# lcd-i2c.net
KiCad netlist of a schematic drawn in EAGLE
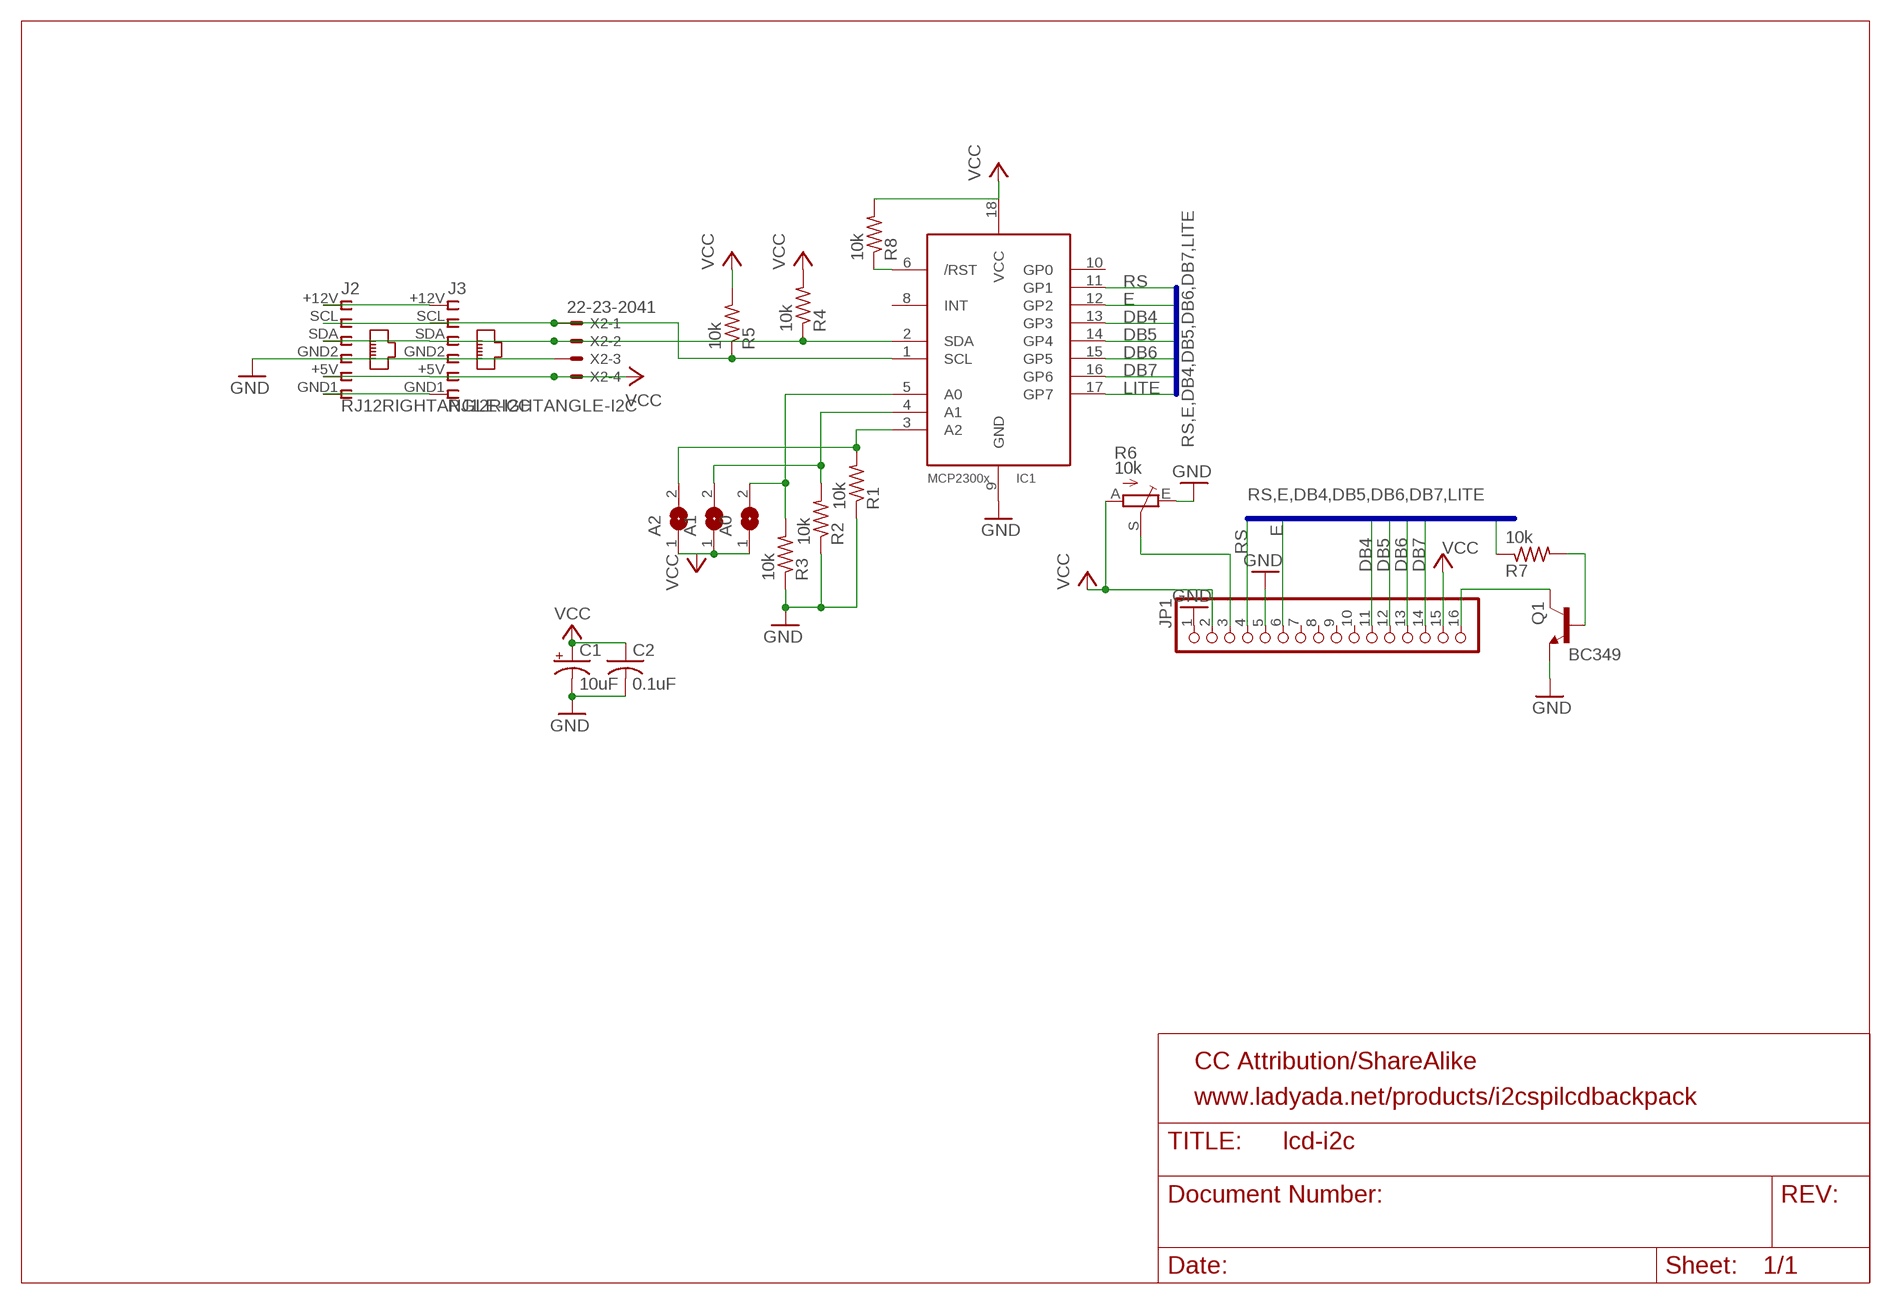
[diagram p0: schematic, sheet 1]

(export (version "E")
  (design (tool "Eeschema 10.0.6"))
  (components
    (comp (ref "A0") (value "SJ") (footprint "eagle-import:SJ") (libsource (lib "eagle-import") (part "SJ")))
    (comp (ref "A1") (value "SJ") (footprint "eagle-import:SJ") (libsource (lib "eagle-import") (part "SJ")))
    (comp (ref "A2") (value "SJ") (footprint "eagle-import:SJ") (libsource (lib "eagle-import") (part "SJ")))
    (comp (ref "C1")
      (value "10uF")
      (footprint "eagle-import:A_3216-18R")
      (libsource (lib "eagle-import") (part "CPOL-USA/3216-18R"))
    )
    (comp (ref "C2")
      (value "0.1uF")
      (footprint "eagle-import:C1206")
      (libsource (lib "eagle-import") (part "C-USC1206"))
    )
    (comp (ref "IC1")
      (value "MCP2300X/P")
      (footprint "eagle-import:DIL18")
      (libsource (lib "eagle-import") (part "MCP2300X/P"))
    )
    (comp (ref "J2")
      (value "RJ12RIGHTANGLE-I2C")
      (footprint "eagle-import:RJ12-RIGHTANGLE-I2C")
      (libsource (lib "eagle-import") (part "RJ12RIGHTANGLE-I2C"))
    )
    (comp (ref "J3")
      (value "RJ12RIGHTANGLE-I2C")
      (footprint "eagle-import:RJ12-RIGHTANGLE-I2C")
      (libsource (lib "eagle-import") (part "RJ12RIGHTANGLE-I2C"))
    )
    (comp (ref "JP1")
      (value "PINHD-1X16")
      (footprint "eagle-import:1X16")
      (libsource (lib "eagle-import") (part "PINHD-1X16"))
    )
    (comp (ref "Q1")
      (value "BC349")
      (footprint "eagle-import:TO92-EBC")
      (libsource (lib "eagle-import") (part "-NPN-TO92-EBCBC317"))
    )
    (comp (ref "R1")
      (value "10k")
      (footprint "eagle-import:M1206")
      (libsource (lib "eagle-import") (part "R-US_M1206"))
    )
    (comp (ref "R2")
      (value "10k")
      (footprint "eagle-import:M1206")
      (libsource (lib "eagle-import") (part "R-US_M1206"))
    )
    (comp (ref "R3")
      (value "10k")
      (footprint "eagle-import:M1206")
      (libsource (lib "eagle-import") (part "R-US_M1206"))
    )
    (comp (ref "R4")
      (value "10k")
      (footprint "eagle-import:M1206")
      (libsource (lib "eagle-import") (part "R-US_M1206"))
    )
    (comp (ref "R5")
      (value "10k")
      (footprint "eagle-import:M1206")
      (libsource (lib "eagle-import") (part "R-US_M1206"))
    )
    (comp (ref "R6")
      (value "10k")
      (footprint "eagle-import:CA6V")
      (libsource (lib "eagle-import") (part "TRIM_EU-CA6V"))
    )
    (comp (ref "R7")
      (value "10k")
      (footprint "eagle-import:M1206")
      (libsource (lib "eagle-import") (part "R-US_M1206"))
    )
    (comp (ref "R8")
      (value "10k")
      (footprint "eagle-import:M1206")
      (libsource (lib "eagle-import") (part "R-US_M1206"))
    )
    (comp (ref "X2")
      (value "22-23-2041")
      (footprint "eagle-import:22-23-2041")
      (fields (field (name "MF") "MOLEX"))
      (libsource (lib "eagle-import") (part "22-23-2041"))
    )
  )
  (nets
    (net (code "1") (name "/DB4") (class "Default")
      (node (ref "IC1") (pin "13") (pinfunction "GP3_13") (pintype "bidirectional"))
      (node (ref "JP1") (pin "11") (pinfunction "11_11") (pintype "passive"))
    )
    (net (code "2") (name "/DB5") (class "Default")
      (node (ref "IC1") (pin "14") (pinfunction "GP4_14") (pintype "bidirectional"))
      (node (ref "JP1") (pin "12") (pinfunction "12_12") (pintype "passive"))
    )
    (net (code "3") (name "/DB6") (class "Default")
      (node (ref "IC1") (pin "15") (pinfunction "GP5_15") (pintype "bidirectional"))
      (node (ref "JP1") (pin "13") (pinfunction "13_13") (pintype "passive"))
    )
    (net (code "4") (name "/DB7") (class "Default")
      (node (ref "IC1") (pin "16") (pinfunction "GP6_16") (pintype "bidirectional"))
      (node (ref "JP1") (pin "14") (pinfunction "14_14") (pintype "passive"))
    )
    (net (code "5") (name "/E") (class "Default")
      (node (ref "IC1") (pin "12") (pinfunction "GP2_12") (pintype "bidirectional"))
      (node (ref "JP1") (pin "6") (pinfunction "6_6") (pintype "passive"))
    )
    (net (code "6") (name "/LITE") (class "Default")
      (node (ref "IC1") (pin "17") (pinfunction "GP7_17") (pintype "bidirectional"))
      (node (ref "R7") (pin "1") (pinfunction "1_1") (pintype "passive"))
    )
    (net (code "7") (name "/RS") (class "Default")
      (node (ref "IC1") (pin "11") (pinfunction "GP1_11") (pintype "bidirectional"))
      (node (ref "JP1") (pin "4") (pinfunction "4_4") (pintype "passive"))
    )
    (net (code "9") (name "GND") (class "Default")
      (node (ref "C1") (pin "-") (pinfunction "-_-") (pintype "passive"))
      (node (ref "C2") (pin "2") (pinfunction "2_2") (pintype "passive"))
      (node (ref "IC1") (pin "9") (pinfunction "GND_9") (pintype "power_in"))
      (node (ref "J2") (pin "GND2") (pinfunction "4_GND2") (pintype "power_in"))
      (node (ref "J3") (pin "GND2") (pinfunction "4_GND2") (pintype "power_in"))
      (node (ref "JP1") (pin "1") (pinfunction "1_1") (pintype "passive"))
      (node (ref "JP1") (pin "5") (pinfunction "5_5") (pintype "passive"))
      (node (ref "Q1") (pin "E") (pinfunction "E_E") (pintype "passive"))
      (node (ref "R1") (pin "1") (pinfunction "1_1") (pintype "passive"))
      (node (ref "R2") (pin "1") (pinfunction "1_1") (pintype "passive"))
      (node (ref "R3") (pin "1") (pinfunction "1_1") (pintype "passive"))
      (node (ref "R6") (pin "E") (pinfunction "E_E") (pintype "passive"))
      (node (ref "X2") (pin "3") (pinfunction "S_3") (pintype "passive"))
    )
    (net (code "10") (name "Net-(IC1-A0)") (class "Default")
      (node (ref "A0") (pin "2") (pinfunction "2_2") (pintype "passive"))
      (node (ref "IC1") (pin "5") (pinfunction "A0_5") (pintype "input"))
      (node (ref "R3") (pin "2") (pinfunction "2_2") (pintype "passive"))
    )
    (net (code "11") (name "Net-(IC1-A1)") (class "Default")
      (node (ref "A1") (pin "2") (pinfunction "2_2") (pintype "passive"))
      (node (ref "IC1") (pin "4") (pinfunction "A1_4") (pintype "input"))
      (node (ref "R2") (pin "2") (pinfunction "2_2") (pintype "passive"))
    )
    (net (code "12") (name "Net-(IC1-A2)") (class "Default")
      (node (ref "A2") (pin "2") (pinfunction "2_2") (pintype "passive"))
      (node (ref "IC1") (pin "3") (pinfunction "A2_3") (pintype "input"))
      (node (ref "R1") (pin "2") (pinfunction "2_2") (pintype "passive"))
    )
    (net (code "13") (name "Net-(IC1-SCL)") (class "Default")
      (node (ref "IC1") (pin "1") (pinfunction "SCL_1") (pintype "bidirectional"))
      (node (ref "J2") (pin "SCL") (pinfunction "2_SCL") (pintype "bidirectional"))
      (node (ref "J3") (pin "SCL") (pinfunction "2_SCL") (pintype "bidirectional"))
      (node (ref "R5") (pin "1") (pinfunction "1_1") (pintype "passive"))
      (node (ref "X2") (pin "1") (pinfunction "S_1") (pintype "passive"))
    )
    (net (code "14") (name "Net-(IC1-SDA)") (class "Default")
      (node (ref "IC1") (pin "2") (pinfunction "SDA_2") (pintype "bidirectional"))
      (node (ref "J2") (pin "SDA") (pinfunction "3_SDA") (pintype "bidirectional"))
      (node (ref "J3") (pin "SDA") (pinfunction "3_SDA") (pintype "bidirectional"))
      (node (ref "R4") (pin "1") (pinfunction "1_1") (pintype "passive"))
      (node (ref "X2") (pin "2") (pinfunction "S_2") (pintype "passive"))
    )
    (net (code "15") (name "Net-(IC1-{slash}RST)") (class "Default")
      (node (ref "IC1") (pin "6") (pinfunction "/RST_6") (pintype "input"))
      (node (ref "R8") (pin "1") (pinfunction "1_1") (pintype "passive"))
    )
    (net (code "16") (name "Net-(J2-1)") (class "Default")
      (node (ref "J2") (pin "+12V") (pinfunction "1_+12V") (pintype "power_in"))
      (node (ref "J3") (pin "+12V") (pinfunction "1_+12V") (pintype "power_in"))
    )
    (net (code "17") (name "Net-(J2-6)") (class "Default")
      (node (ref "J2") (pin "GND1") (pinfunction "6_GND1") (pintype "power_in"))
      (node (ref "J3") (pin "GND1") (pinfunction "6_GND1") (pintype "power_in"))
    )
    (net (code "18") (name "Net-(JP1-Pad3)") (class "Default")
      (node (ref "JP1") (pin "3") (pinfunction "3_3") (pintype "passive"))
      (node (ref "R6") (pin "S") (pinfunction "S_S") (pintype "passive"))
    )
    (net (code "19") (name "Net-(JP1-Pad16)") (class "Default")
      (node (ref "JP1") (pin "16") (pinfunction "16_16") (pintype "passive"))
      (node (ref "Q1") (pin "C") (pinfunction "C_C") (pintype "passive"))
    )
    (net (code "20") (name "Net-(Q1-PadB)") (class "Default")
      (node (ref "Q1") (pin "B") (pinfunction "B_B") (pintype "passive"))
      (node (ref "R7") (pin "2") (pinfunction "2_2") (pintype "passive"))
    )
    (net (code "21") (name "VCC") (class "Default")
      (node (ref "A0") (pin "1") (pinfunction "1_1") (pintype "passive"))
      (node (ref "A1") (pin "1") (pinfunction "1_1") (pintype "passive"))
      (node (ref "A2") (pin "1") (pinfunction "1_1") (pintype "passive"))
      (node (ref "C1") (pin "+") (pinfunction "+_+") (pintype "passive"))
      (node (ref "C2") (pin "1") (pinfunction "1_1") (pintype "passive"))
      (node (ref "IC1") (pin "18") (pinfunction "VCC_18") (pintype "power_in"))
      (node (ref "J2") (pin "+5V") (pinfunction "5_+5V") (pintype "power_in"))
      (node (ref "J3") (pin "+5V") (pinfunction "5_+5V") (pintype "power_in"))
      (node (ref "JP1") (pin "15") (pinfunction "15_15") (pintype "passive"))
      (node (ref "JP1") (pin "2") (pinfunction "2_2") (pintype "passive"))
      (node (ref "R4") (pin "2") (pinfunction "2_2") (pintype "passive"))
      (node (ref "R5") (pin "2") (pinfunction "2_2") (pintype "passive"))
      (node (ref "R6") (pin "A") (pinfunction "A_A") (pintype "passive"))
      (node (ref "R8") (pin "2") (pinfunction "2_2") (pintype "passive"))
      (node (ref "X2") (pin "4") (pinfunction "S_4") (pintype "passive"))
    )
    (net (code "22") (name "unconnected-(IC1-GP0-Pad10)") (class "Default")
      (node (ref "IC1") (pin "10") (pinfunction "GP0_10") (pintype "bidirectional"))
    )
    (net (code "23") (name "unconnected-(IC1-INT-Pad8)") (class "Default")
      (node (ref "IC1") (pin "8") (pinfunction "INT_8") (pintype "output"))
    )
    (net (code "24") (name "unconnected-(JP1-Pad7)") (class "Default")
      (node (ref "JP1") (pin "7") (pinfunction "7_7") (pintype "passive"))
    )
    (net (code "25") (name "unconnected-(JP1-Pad8)") (class "Default")
      (node (ref "JP1") (pin "8") (pinfunction "8_8") (pintype "passive"))
    )
    (net (code "26") (name "unconnected-(JP1-Pad9)") (class "Default")
      (node (ref "JP1") (pin "9") (pinfunction "9_9") (pintype "passive"))
    )
    (net (code "27") (name "unconnected-(JP1-Pad10)") (class "Default")
      (node (ref "JP1") (pin "10") (pinfunction "10_10") (pintype "passive"))
    )
  )
)
